# PGA.net
KiCad netlist of a schematic drawn in Altium Designer
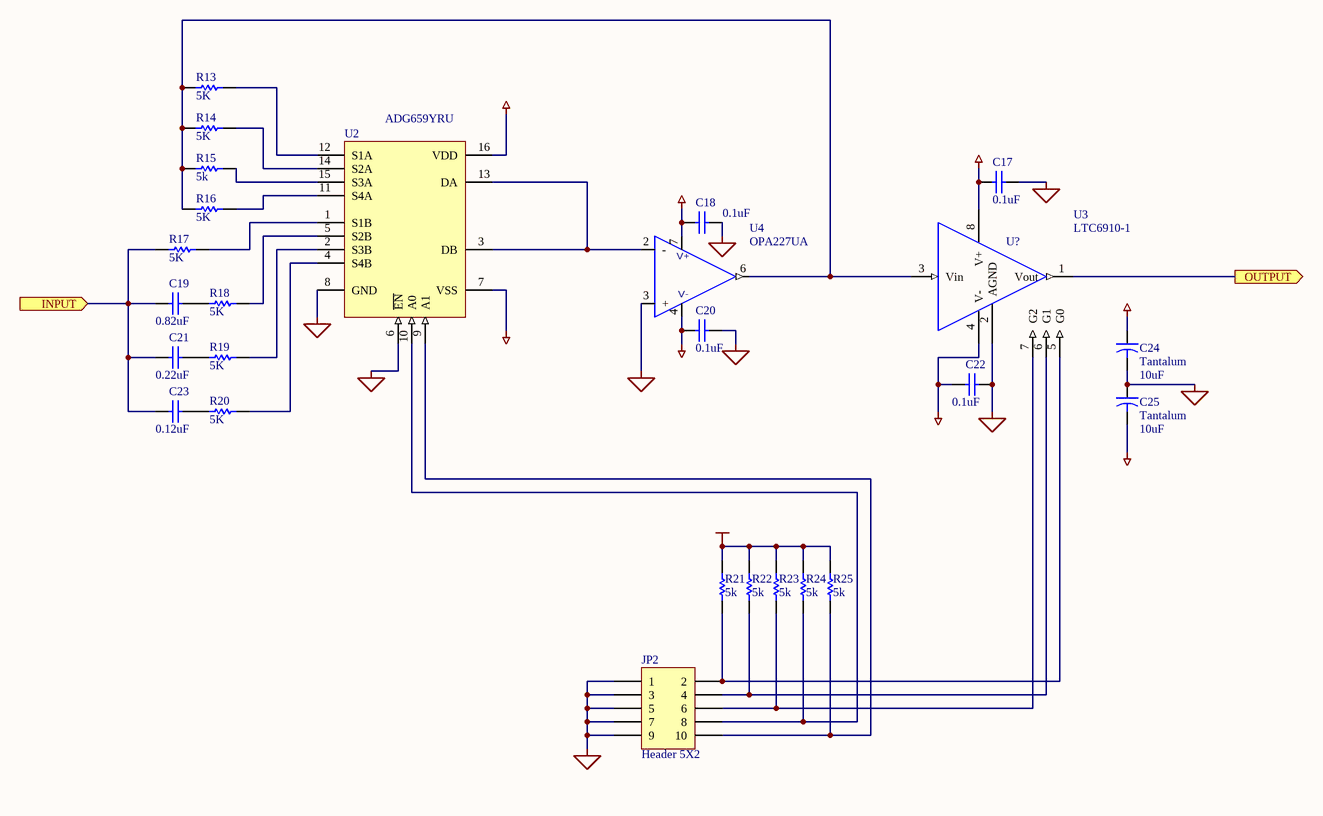
[diagram p0: PGA.SCHDOC]

(export (version "E")
  (design (tool "Eeschema 10.0.6"))
  (components
    (comp (ref "C17")
      (value "Cap")
      (footprint "CC1608-0603")
      (description "Capacitor")
      (fields
        (field (name "MANUFACTURER") "Generic Components")
        (field (name "ALTIUM_VALUE") "0.1uF")
        (field (name "PUBLISHER") "Altium Limited")
      )
      (libsource (lib "Miscellaneous Devices") (part "Cap"))
    )
    (comp (ref "C18")
      (value "Cap")
      (footprint "CC1608-0603")
      (description "Capacitor")
      (fields
        (field (name "MANUFACTURER") "Generic Components")
        (field (name "ALTIUM_VALUE") "0.1uF")
        (field (name "PUBLISHER") "Altium Limited")
      )
      (libsource (lib "Miscellaneous Devices") (part "Cap"))
    )
    (comp (ref "C19")
      (value "Cap")
      (footprint "CC1608-0603")
      (description "Capacitor")
      (fields
        (field (name "MANUFACTURER") "Generic Components")
        (field (name "ALTIUM_VALUE") "0.82uF")
        (field (name "PUBLISHER") "Altium Limited")
      )
      (libsource (lib "Miscellaneous Devices") (part "Cap"))
    )
    (comp (ref "C20")
      (value "Cap")
      (footprint "CC1608-0603")
      (description "Capacitor")
      (fields
        (field (name "MANUFACTURER") "Generic Components")
        (field (name "ALTIUM_VALUE") "0.1uF")
        (field (name "PUBLISHER") "Altium Limited")
      )
      (libsource (lib "Miscellaneous Devices") (part "Cap"))
    )
    (comp (ref "C21")
      (value "Cap")
      (footprint "CC1608-0603")
      (description "Capacitor")
      (fields
        (field (name "MANUFACTURER") "Generic Components")
        (field (name "ALTIUM_VALUE") "0.22uF")
        (field (name "PUBLISHER") "Altium Limited")
      )
      (libsource (lib "Miscellaneous Devices") (part "Cap"))
    )
    (comp (ref "C22")
      (value "Cap")
      (footprint "CC1608-0603")
      (description "Capacitor")
      (fields
        (field (name "MANUFACTURER") "Generic Components")
        (field (name "ALTIUM_VALUE") "0.1uF")
        (field (name "PUBLISHER") "Altium Limited")
      )
      (libsource (lib "Miscellaneous Devices") (part "Cap"))
    )
    (comp (ref "C23")
      (value "Cap")
      (footprint "CC1608-0603")
      (description "Capacitor")
      (fields
        (field (name "MANUFACTURER") "Generic Components")
        (field (name "ALTIUM_VALUE") "0.12uF")
        (field (name "PUBLISHER") "Altium Limited")
      )
      (libsource (lib "Miscellaneous Devices") (part "Cap"))
    )
    (comp (ref "C24")
      (value "Tantalum")
      (footprint "TC3216-1206")
      (description "Capacitor")
      (fields
        (field (name "MANUFACTURER") "Generic Components")
        (field (name "ALTIUM_VALUE") "10uF")
        (field (name "PUBLISHER") "Altium Limited")
      )
      (libsource (lib "Miscellaneous Devices") (part "Cap2"))
    )
    (comp (ref "C25")
      (value "Tantalum")
      (footprint "TC3216-1206")
      (description "Capacitor")
      (fields
        (field (name "MANUFACTURER") "Generic Components")
        (field (name "ALTIUM_VALUE") "10uF")
        (field (name "PUBLISHER") "Altium Limited")
      )
      (libsource (lib "Miscellaneous Devices") (part "Cap2"))
    )
    (comp (ref "JP2")
      (value "Header 5X2")
      (footprint "HDR2X5")
      (description "Header, 5-Pin, Dual row")
      (fields (field (name "MANUFACTURER") "Generic Components") (field (name "PUBLISHER") "Altium Limited"))
      (libsource (lib "Miscellaneous Connectors") (part "Header 5X2"))
    )
    (comp (ref "R13")
      (value "Res1")
      (footprint "KEMET Chip Capacitor:CC1608-0603")
      (description "Resistor")
      (fields
        (field (name "MANUFACTURER") "Generic Components")
        (field (name "ALTIUM_VALUE") "5K")
        (field (name "PUBLISHER") "Altium Limited")
      )
      (libsource (lib "Miscellaneous Devices") (part "Res1"))
    )
    (comp (ref "R14")
      (value "Res1")
      (footprint "KEMET Chip Capacitor:CC1608-0603")
      (description "Resistor")
      (fields
        (field (name "MANUFACTURER") "Generic Components")
        (field (name "ALTIUM_VALUE") "5K")
        (field (name "PUBLISHER") "Altium Limited")
      )
      (libsource (lib "Miscellaneous Devices") (part "Res1"))
    )
    (comp (ref "R15")
      (value "Res1")
      (footprint "KEMET Chip Capacitor:CC1608-0603")
      (description "Resistor")
      (fields
        (field (name "MANUFACTURER") "Generic Components")
        (field (name "ALTIUM_VALUE") "5k")
        (field (name "PUBLISHER") "Altium Limited")
      )
      (libsource (lib "Miscellaneous Devices") (part "Res1"))
    )
    (comp (ref "R16")
      (value "Res1")
      (footprint "KEMET Chip Capacitor:CC1608-0603")
      (description "Resistor")
      (fields
        (field (name "MANUFACTURER") "Generic Components")
        (field (name "ALTIUM_VALUE") "5K")
        (field (name "PUBLISHER") "Altium Limited")
      )
      (libsource (lib "Miscellaneous Devices") (part "Res1"))
    )
    (comp (ref "R17")
      (value "Res1")
      (footprint "KEMET Chip Capacitor:CC1608-0603")
      (description "Resistor")
      (fields
        (field (name "MANUFACTURER") "Generic Components")
        (field (name "ALTIUM_VALUE") "5K")
        (field (name "PUBLISHER") "Altium Limited")
      )
      (libsource (lib "Miscellaneous Devices") (part "Res1"))
    )
    (comp (ref "R18")
      (value "Res1")
      (footprint "KEMET Chip Capacitor:CC1608-0603")
      (description "Resistor")
      (fields
        (field (name "MANUFACTURER") "Generic Components")
        (field (name "ALTIUM_VALUE") "5K")
        (field (name "PUBLISHER") "Altium Limited")
      )
      (libsource (lib "Miscellaneous Devices") (part "Res1"))
    )
    (comp (ref "R19")
      (value "Res1")
      (footprint "KEMET Chip Capacitor:CC1608-0603")
      (description "Resistor")
      (fields
        (field (name "MANUFACTURER") "Generic Components")
        (field (name "ALTIUM_VALUE") "5K")
        (field (name "PUBLISHER") "Altium Limited")
      )
      (libsource (lib "Miscellaneous Devices") (part "Res1"))
    )
    (comp (ref "R20")
      (value "Res1")
      (footprint "KEMET Chip Capacitor:CC1608-0603")
      (description "Resistor")
      (fields
        (field (name "MANUFACTURER") "Generic Components")
        (field (name "ALTIUM_VALUE") "5K")
        (field (name "PUBLISHER") "Altium Limited")
      )
      (libsource (lib "Miscellaneous Devices") (part "Res1"))
    )
    (comp (ref "R21")
      (value "Res1")
      (footprint "CC2012-0805")
      (description "Resistor")
      (fields
        (field (name "MANUFACTURER") "Generic Components")
        (field (name "ALTIUM_VALUE") "5k")
        (field (name "PUBLISHER") "Altium Limited")
      )
      (libsource (lib "Miscellaneous Devices") (part "Res1"))
    )
    (comp (ref "R22")
      (value "Res1")
      (footprint "CC2012-0805")
      (description "Resistor")
      (fields
        (field (name "MANUFACTURER") "Generic Components")
        (field (name "ALTIUM_VALUE") "5k")
        (field (name "PUBLISHER") "Altium Limited")
      )
      (libsource (lib "Miscellaneous Devices") (part "Res1"))
    )
    (comp (ref "R23")
      (value "Res1")
      (footprint "CC2012-0805")
      (description "Resistor")
      (fields
        (field (name "MANUFACTURER") "Generic Components")
        (field (name "ALTIUM_VALUE") "5k")
        (field (name "PUBLISHER") "Altium Limited")
      )
      (libsource (lib "Miscellaneous Devices") (part "Res1"))
    )
    (comp (ref "R24")
      (value "Res1")
      (footprint "CC2012-0805")
      (description "Resistor")
      (fields
        (field (name "MANUFACTURER") "Generic Components")
        (field (name "ALTIUM_VALUE") "5k")
        (field (name "PUBLISHER") "Altium Limited")
      )
      (libsource (lib "Miscellaneous Devices") (part "Res1"))
    )
    (comp (ref "R25")
      (value "Res1")
      (footprint "CC2012-0805")
      (description "Resistor")
      (fields
        (field (name "MANUFACTURER") "Generic Components")
        (field (name "ALTIUM_VALUE") "5k")
        (field (name "PUBLISHER") "Altium Limited")
      )
      (libsource (lib "Miscellaneous Devices") (part "Res1"))
    )
    (comp (ref "U2")
      (value "ADG659YRU")
      (footprint "TSSO5X6-G16")
      (description "ADG659 4:1 Differential +/- 5V Mux")
      (libsource (lib "My devices") (part "ADG659"))
    )
    (comp (ref "U3")
      (value "LTC6910-1")
      (footprint "TSOT-23-8")
      (description "LTI Digitally Controlled Programmabe Gain Amp")
      (libsource (lib "My devices") (part "LTC6910-2"))
    )
    (comp (ref "U4")
      (value "OPA227UA")
      (footprint "SO-G8/D5.1")
      (libsource (lib "My devices") (part "OPA227UA"))
    )
  )
  (nets
    (net (code "1") (name "/INPUT") (class "Default")
      (node (ref "C19") (pin "2") (pinfunction "2_2") (pintype "passive"))
      (node (ref "C21") (pin "2") (pinfunction "2_2") (pintype "passive"))
      (node (ref "C23") (pin "2") (pinfunction "2_2") (pintype "passive"))
      (node (ref "R17") (pin "1") (pinfunction "1_1") (pintype "passive"))
    )
    (net (code "2") (name "/OUTPUT") (class "Default")
      (node (ref "U3") (pin "1") (pinfunction "Vout_1") (pintype "output"))
    )
    (net (code "3") (name "AVDD") (class "Default")
      (node (ref "C17") (pin "1") (pinfunction "1_1") (pintype "passive"))
      (node (ref "C18") (pin "2") (pinfunction "2_2") (pintype "passive"))
      (node (ref "C24") (pin "1") (pinfunction "1_1") (pintype "passive"))
      (node (ref "R21") (pin "2") (pinfunction "2_2") (pintype "passive"))
      (node (ref "R22") (pin "2") (pinfunction "2_2") (pintype "passive"))
      (node (ref "R23") (pin "2") (pinfunction "2_2") (pintype "passive"))
      (node (ref "R24") (pin "2") (pinfunction "2_2") (pintype "passive"))
      (node (ref "R25") (pin "2") (pinfunction "2_2") (pintype "passive"))
      (node (ref "U2") (pin "16") (pinfunction "VDD_16") (pintype "power_in"))
      (node (ref "U3") (pin "8") (pinfunction "V+_8") (pintype "power_in"))
      (node (ref "U4") (pin "7") (pinfunction "V+_7") (pintype "power_in"))
    )
    (net (code "4") (name "AVSS") (class "Default")
      (node (ref "C20") (pin "2") (pinfunction "2_2") (pintype "passive"))
      (node (ref "C22") (pin "2") (pinfunction "2_2") (pintype "passive"))
      (node (ref "C25") (pin "2") (pinfunction "2_2") (pintype "passive"))
      (node (ref "U2") (pin "7") (pinfunction "VSS_7") (pintype "power_in"))
      (node (ref "U3") (pin "4") (pinfunction "V-_4") (pintype "power_in"))
      (node (ref "U4") (pin "4") (pinfunction "V-_4") (pintype "power_in"))
    )
    (net (code "5") (name "GND") (class "Default")
      (node (ref "C17") (pin "2") (pinfunction "2_2") (pintype "passive"))
      (node (ref "C18") (pin "1") (pinfunction "1_1") (pintype "passive"))
      (node (ref "C20") (pin "1") (pinfunction "1_1") (pintype "passive"))
      (node (ref "C22") (pin "1") (pinfunction "1_1") (pintype "passive"))
      (node (ref "C24") (pin "2") (pinfunction "2_2") (pintype "passive"))
      (node (ref "C25") (pin "1") (pinfunction "1_1") (pintype "passive"))
      (node (ref "JP2") (pin "1") (pinfunction "1_1") (pintype "passive"))
      (node (ref "JP2") (pin "3") (pinfunction "3_3") (pintype "passive"))
      (node (ref "JP2") (pin "5") (pinfunction "5_5") (pintype "passive"))
      (node (ref "JP2") (pin "7") (pinfunction "7_7") (pintype "passive"))
      (node (ref "JP2") (pin "9") (pinfunction "9_9") (pintype "passive"))
      (node (ref "U2") (pin "6") (pinfunction "~{EN}_6") (pintype "input"))
      (node (ref "U2") (pin "8") (pinfunction "GND_8") (pintype "power_in"))
      (node (ref "U3") (pin "2") (pinfunction "AGND_2") (pintype "power_in"))
      (node (ref "U4") (pin "3") (pinfunction "+_3") (pintype "passive"))
    )
    (net (code "6") (name "Net-(C19-Pad1)") (class "Default")
      (node (ref "C19") (pin "1") (pinfunction "1_1") (pintype "passive"))
      (node (ref "R18") (pin "1") (pinfunction "1_1") (pintype "passive"))
    )
    (net (code "7") (name "Net-(C21-Pad1)") (class "Default")
      (node (ref "C21") (pin "1") (pinfunction "1_1") (pintype "passive"))
      (node (ref "R19") (pin "1") (pinfunction "1_1") (pintype "passive"))
    )
    (net (code "8") (name "Net-(C23-Pad1)") (class "Default")
      (node (ref "C23") (pin "1") (pinfunction "1_1") (pintype "passive"))
      (node (ref "R20") (pin "1") (pinfunction "1_1") (pintype "passive"))
    )
    (net (code "9") (name "Net-(U2-A0)") (class "Default")
      (node (ref "JP2") (pin "8") (pinfunction "8_8") (pintype "passive"))
      (node (ref "R24") (pin "1") (pinfunction "1_1") (pintype "passive"))
      (node (ref "U2") (pin "10") (pinfunction "A0_10") (pintype "input"))
    )
    (net (code "10") (name "Net-(U2-A1)") (class "Default")
      (node (ref "JP2") (pin "10") (pinfunction "10_10") (pintype "passive"))
      (node (ref "R25") (pin "1") (pinfunction "1_1") (pintype "passive"))
      (node (ref "U2") (pin "9") (pinfunction "A1_9") (pintype "input"))
    )
    (net (code "11") (name "Net-(U2-DA)") (class "Default")
      (node (ref "U2") (pin "13") (pinfunction "DA_13") (pintype "passive"))
      (node (ref "U2") (pin "3") (pinfunction "DB_3") (pintype "passive"))
      (node (ref "U4") (pin "2") (pinfunction "-_2") (pintype "passive"))
    )
    (net (code "12") (name "Net-(U2-S1A)") (class "Default")
      (node (ref "R13") (pin "2") (pinfunction "2_2") (pintype "passive"))
      (node (ref "U2") (pin "12") (pinfunction "S1A_12") (pintype "passive"))
    )
    (net (code "13") (name "Net-(U2-S1B)") (class "Default")
      (node (ref "R17") (pin "2") (pinfunction "2_2") (pintype "passive"))
      (node (ref "U2") (pin "1") (pinfunction "S1B_1") (pintype "passive"))
    )
    (net (code "14") (name "Net-(U2-S2A)") (class "Default")
      (node (ref "R14") (pin "2") (pinfunction "2_2") (pintype "passive"))
      (node (ref "U2") (pin "14") (pinfunction "S2A_14") (pintype "passive"))
    )
    (net (code "15") (name "Net-(U2-S2B)") (class "Default")
      (node (ref "R18") (pin "2") (pinfunction "2_2") (pintype "passive"))
      (node (ref "U2") (pin "5") (pinfunction "S2B_5") (pintype "passive"))
    )
    (net (code "16") (name "Net-(U2-S3A)") (class "Default")
      (node (ref "R15") (pin "2") (pinfunction "2_2") (pintype "passive"))
      (node (ref "U2") (pin "15") (pinfunction "S3A_15") (pintype "passive"))
    )
    (net (code "17") (name "Net-(U2-S3B)") (class "Default")
      (node (ref "R19") (pin "2") (pinfunction "2_2") (pintype "passive"))
      (node (ref "U2") (pin "2") (pinfunction "S3B_2") (pintype "passive"))
    )
    (net (code "18") (name "Net-(U2-S4A)") (class "Default")
      (node (ref "R16") (pin "2") (pinfunction "2_2") (pintype "passive"))
      (node (ref "U2") (pin "11") (pinfunction "S4A_11") (pintype "passive"))
    )
    (net (code "19") (name "Net-(U2-S4B)") (class "Default")
      (node (ref "R20") (pin "2") (pinfunction "2_2") (pintype "passive"))
      (node (ref "U2") (pin "4") (pinfunction "S4B_4") (pintype "passive"))
    )
    (net (code "20") (name "Net-(U3-G0)") (class "Default")
      (node (ref "JP2") (pin "2") (pinfunction "2_2") (pintype "passive"))
      (node (ref "R21") (pin "1") (pinfunction "1_1") (pintype "passive"))
      (node (ref "U3") (pin "5") (pinfunction "G0_5") (pintype "input"))
    )
    (net (code "21") (name "Net-(U3-G1)") (class "Default")
      (node (ref "JP2") (pin "4") (pinfunction "4_4") (pintype "passive"))
      (node (ref "R22") (pin "1") (pinfunction "1_1") (pintype "passive"))
      (node (ref "U3") (pin "6") (pinfunction "G1_6") (pintype "input"))
    )
    (net (code "22") (name "Net-(U3-G2)") (class "Default")
      (node (ref "JP2") (pin "6") (pinfunction "6_6") (pintype "passive"))
      (node (ref "R23") (pin "1") (pinfunction "1_1") (pintype "passive"))
      (node (ref "U3") (pin "7") (pinfunction "G2_7") (pintype "input"))
    )
    (net (code "23") (name "Net-(U3-Vin)") (class "Default")
      (node (ref "R13") (pin "1") (pinfunction "1_1") (pintype "passive"))
      (node (ref "R14") (pin "1") (pinfunction "1_1") (pintype "passive"))
      (node (ref "R15") (pin "1") (pinfunction "1_1") (pintype "passive"))
      (node (ref "R16") (pin "1") (pinfunction "1_1") (pintype "passive"))
      (node (ref "U3") (pin "3") (pinfunction "Vin_3") (pintype "input"))
      (node (ref "U4") (pin "6") (pinfunction "Vout_6") (pintype "output"))
    )
  )
)
